# NOT-B.net
KiCad netlist of a schematic drawn in EAGLE
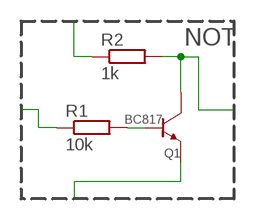
[diagram p0: schematic, sheet 1]

(export (version "E")
  (design (tool "Eeschema 10.0.6"))
  (components
    (comp (ref "Q1")
      (value "BC817")
      (footprint "eagle-import:SOT23")
      (libsource (lib "eagle-import") (part "TRANSISTOR-NPN-GENERIC-SOT23-BECDEFAULT"))
    )
    (comp (ref "R1")
      (value "10k")
      (footprint "eagle-import:R0603")
      (libsource (lib "eagle-import") (part "R-EU_R0603"))
    )
    (comp (ref "R2")
      (value "1k")
      (footprint "eagle-import:R0603")
      (libsource (lib "eagle-import") (part "R-EU_R0603"))
    )
  )
  (nets
    (net (code "1") (name "Net-(Q1-BASE)") (class "Default")
      (node (ref "Q1") (pin "P$1") (pinfunction "BASE_P$1") (pintype "bidirectional"))
      (node (ref "R1") (pin "2") (pinfunction "2_2") (pintype "passive"))
    )
    (net (code "2") (name "Net-(Q1-COLLECTOR)") (class "Default")
      (node (ref "Q1") (pin "P$3") (pinfunction "COLLECTOR_P$3") (pintype "bidirectional"))
      (node (ref "R2") (pin "2") (pinfunction "2_2") (pintype "passive"))
    )
    (net (code "3") (name "unconnected-(Q1-EMITTER-PadP$2)") (class "Default")
      (node (ref "Q1") (pin "P$2") (pinfunction "EMITTER_P$2") (pintype "bidirectional"))
    )
    (net (code "4") (name "unconnected-(R1-Pad1)") (class "Default")
      (node (ref "R1") (pin "1") (pinfunction "1_1") (pintype "passive"))
    )
    (net (code "5") (name "unconnected-(R2-Pad1)") (class "Default")
      (node (ref "R2") (pin "1") (pinfunction "1_1") (pintype "passive"))
    )
  )
)
